# USR_IO_IPMI.net
KiCad netlist of a schematic drawn in Altium Designer
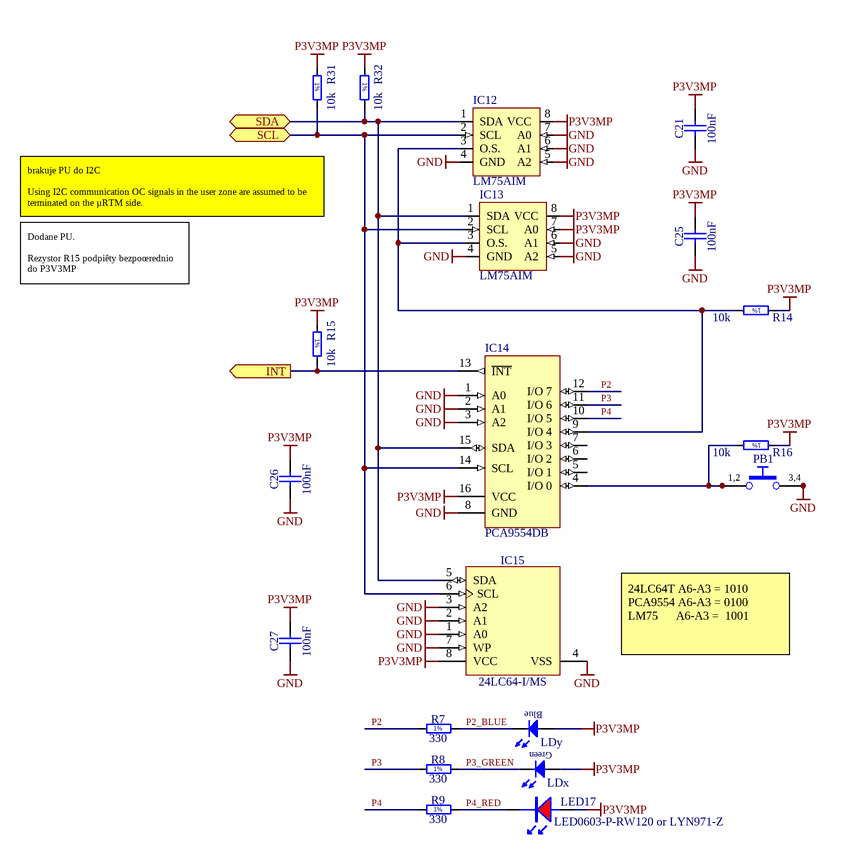
[diagram p0: USR_IO_IPMI.SchDoc]

(export (version "E")
  (design (tool "Eeschema 10.0.6"))
  (components
    (comp (ref "C21")
      (value "100nF")
      (footprint "CAPC1005X55N")
      (description "Non-polarised capacitor")
      (fields
        (field (name "PART NUMBER") "CC0402_100NF_16V_10%_X7R")
        (field (name "VOLTAGE") "16V")
        (field (name "AUTHOR") "CERN DEM JLC")
      )
      (libsource (lib "Capacitors") (part "Capacitor - non polarized"))
    )
    (comp (ref "C25")
      (value "100nF")
      (footprint "CAPC1005X55N")
      (description "Non-polarised capacitor")
      (fields
        (field (name "PART NUMBER") "CC0402_100NF_16V_10%_X7R")
        (field (name "VOLTAGE") "16V")
        (field (name "AUTHOR") "CERN DEM JLC")
      )
      (libsource (lib "Capacitors") (part "Capacitor - non polarized"))
    )
    (comp (ref "C26")
      (value "100nF")
      (footprint "CAPC1005X55N")
      (description "Non-polarised capacitor")
      (fields
        (field (name "PART NUMBER") "CC0402_100NF_16V_10%_X7R")
        (field (name "VOLTAGE") "16V")
        (field (name "AUTHOR") "CERN DEM JLC")
      )
      (libsource (lib "Capacitors") (part "Capacitor - non polarized"))
    )
    (comp (ref "C27")
      (value "100nF")
      (footprint "CAPC1005X55N")
      (description "Non-polarised capacitor")
      (fields
        (field (name "PART NUMBER") "CC0402_100NF_16V_10%_X7R")
        (field (name "VOLTAGE") "16V")
        (field (name "AUTHOR") "CERN DEM JLC")
      )
      (libsource (lib "Capacitors") (part "Capacitor - non polarized"))
    )
    (comp (ref "IC12")
      (value "LM75AIM")
      (footprint "SOIC127P600X175-8N")
      (description "I2C temperature sensor")
      (libsource (lib "LIBRARY_SCH") (part "SENS_LM75"))
    )
    (comp (ref "IC13")
      (value "LM75AIM")
      (footprint "SOIC127P600X175-8N")
      (description "I2C temperature sensor")
      (libsource (lib "LIBRARY_SCH") (part "SENS_LM75"))
    )
    (comp (ref "IC14")
      (value "PCA9554DB")
      (footprint "SOP65P640X120-16N")
      (description "8-bit I2C-bus SMBus I/O port with interrupt")
      (libsource (lib "wr_switch") (part "PCA9554D"))
    )
    (comp (ref "IC15")
      (value "24LC64-I/MS")
      (footprint "SOP65P490X110-8N")
      (description "64K I2C Serial EEPROM")
      (fields (field (name "MANUFACTURER") "MICROCHIP TECHNOLOGY") (field (name "AUTHOR") "CERN DEM JLC"))
      (libsource (lib "ICs And Semiconductors") (part "24LC64-I/MS"))
    )
    (comp (ref "LDx")
      (value "Green")
      (footprint "LED_AVAGO_HSME-C120")
      (description "LED Green Avago C120")
      (fields
        (field (name "PART NUMBER") "LED_AVAGO_HSME-C120")
        (field (name "MANUFACTURER") "AVAGO TECHNOLOGIES")
        (field (name "AUTHOR") "CERN DEM JMW")
      )
      (libsource (lib "LIBRARY_SCH") (part "LED_SMD_90deg_mini_G"))
    )
    (comp (ref "LDy")
      (value "Blue")
      (footprint "LED_AVAGO_HSME-C120")
      (description "LED Blue Avago C120")
      (fields
        (field (name "PART NUMBER") "LED_AVAGO_HSMR-C120")
        (field (name "MANUFACTURER") "AVAGO TECHNOLOGIES")
        (field (name "AUTHOR") "CERN DEM JMW")
      )
      (libsource (lib "LIBRARY_SCH") (part "LED_SMD_90deg_mini_B"))
    )
    (comp (ref "LED17")
      (value "LED0603-P-RW120 or LYN971-Z")
      (footprint "led_0603R")
      (description "LED 0603 red")
      (libsource (lib "LIBRARY_SCH") (part "LED_0603R"))
    )
    (comp (ref "PB1")
      (value "Push Button")
      (footprint "SW_C&K_HDT0001")
      (description "Push-Button Switch SPDT")
      (fields
        (field (name "PART NUMBER") "SW_C&K_HDT0001")
        (field (name "MANUFACTURER") "C&K")
        (field (name "AUTHOR") "CERN DEM JLC")
      )
      (libsource (lib "Eletro-mechanical") (part "PB SPST 12NO-34NO"))
    )
    (comp (ref "R7")
      (value "330")
      (footprint "RESC1608X55N")
      (description "Resistor - 1%")
      (fields
        (field (name "PART NUMBER") "R0603_330R_1%_0.1W_100PPM")
        (field (name "POWER") "0.1W")
        (field (name "AUTHOR") "CERN DEM JLC")
      )
      (libsource (lib "Resistors") (part "Resistor - 1%"))
    )
    (comp (ref "R8")
      (value "330")
      (footprint "RESC1608X55N")
      (description "Resistor - 1%")
      (fields
        (field (name "PART NUMBER") "R0603_330R_1%_0.1W_100PPM")
        (field (name "POWER") "0.1W")
        (field (name "AUTHOR") "CERN DEM JLC")
      )
      (libsource (lib "Resistors") (part "Resistor - 1%"))
    )
    (comp (ref "R9")
      (value "330")
      (footprint "RESC1608X55N")
      (description "Resistor - 1%")
      (fields
        (field (name "PART NUMBER") "R0603_330R_1%_0.1W_100PPM")
        (field (name "POWER") "0.1W")
        (field (name "AUTHOR") "CERN DEM JLC")
      )
      (libsource (lib "Resistors") (part "Resistor - 1%"))
    )
    (comp (ref "R14")
      (value "10k")
      (footprint "RESC1005X40N")
      (description "Resistor - 1%")
      (fields
        (field (name "PART NUMBER") "R0402_10K_1%_0.0625W_100PPM")
        (field (name "POWER") "0.0625W")
        (field (name "AUTHOR") "CERN DEM JLC")
      )
      (libsource (lib "Resistors") (part "Resistor - 1%"))
    )
    (comp (ref "R15")
      (value "10k")
      (footprint "RESC1005X40N")
      (description "Resistor - 1%")
      (fields
        (field (name "PART NUMBER") "R0402_10K_1%_0.0625W_100PPM")
        (field (name "POWER") "0.0625W")
        (field (name "AUTHOR") "CERN DEM JLC")
      )
      (libsource (lib "Resistors") (part "Resistor - 1%"))
    )
    (comp (ref "R16")
      (value "10k")
      (footprint "RESC1005X40N")
      (description "Resistor - 1%")
      (fields
        (field (name "PART NUMBER") "R0402_10K_1%_0.0625W_100PPM")
        (field (name "POWER") "0.0625W")
        (field (name "AUTHOR") "CERN DEM JLC")
      )
      (libsource (lib "Resistors") (part "Resistor - 1%"))
    )
    (comp (ref "R31")
      (value "10k")
      (footprint "RESC1005X40N")
      (description "Resistor - 1%")
      (fields
        (field (name "PART NUMBER") "R0402_10K_1%_0.0625W_100PPM")
        (field (name "POWER") "0.0625W")
        (field (name "AUTHOR") "CERN DEM JLC")
      )
      (libsource (lib "Resistors") (part "Resistor - 1%"))
    )
    (comp (ref "R32")
      (value "10k")
      (footprint "RESC1005X40N")
      (description "Resistor - 1%")
      (fields
        (field (name "PART NUMBER") "R0402_10K_1%_0.0625W_100PPM")
        (field (name "POWER") "0.0625W")
        (field (name "AUTHOR") "CERN DEM JLC")
      )
      (libsource (lib "Resistors") (part "Resistor - 1%"))
    )
  )
  (nets
    (net (code "1") (name "/INT") (class "Default")
      (node (ref "IC14") (pin "13") (pinfunction "~{INT}_13") (pintype "output"))
      (node (ref "R15") (pin "2") (pinfunction "2_2") (pintype "passive"))
    )
    (net (code "2") (name "/P2") (class "Default")
      (node (ref "IC14") (pin "12") (pinfunction "I/O_7_12") (pintype "bidirectional"))
      (node (ref "R7") (pin "1") (pinfunction "1_1") (pintype "passive"))
    )
    (net (code "3") (name "/P2_BLUE") (class "Default")
      (node (ref "LDy") (pin "2") (pinfunction "C_2") (pintype "passive"))
      (node (ref "R7") (pin "2") (pinfunction "2_2") (pintype "passive"))
    )
    (net (code "4") (name "/P3") (class "Default")
      (node (ref "IC14") (pin "11") (pinfunction "I/O_6_11") (pintype "bidirectional"))
      (node (ref "R8") (pin "1") (pinfunction "1_1") (pintype "passive"))
    )
    (net (code "5") (name "/P3_GREEN") (class "Default")
      (node (ref "LDx") (pin "2") (pinfunction "C_2") (pintype "passive"))
      (node (ref "R8") (pin "2") (pinfunction "2_2") (pintype "passive"))
    )
    (net (code "6") (name "/P4") (class "Default")
      (node (ref "IC14") (pin "10") (pinfunction "I/O_5_10") (pintype "bidirectional"))
      (node (ref "R9") (pin "1") (pinfunction "1_1") (pintype "passive"))
    )
    (net (code "7") (name "/P4_RED") (class "Default")
      (node (ref "LED17") (pin "K") (pinfunction "K_K") (pintype "passive"))
      (node (ref "R9") (pin "2") (pinfunction "2_2") (pintype "passive"))
    )
    (net (code "8") (name "/SCL") (class "Default")
      (node (ref "IC12") (pin "2") (pinfunction "SCL_2") (pintype "input"))
      (node (ref "IC13") (pin "2") (pinfunction "SCL_2") (pintype "input"))
      (node (ref "IC14") (pin "14") (pinfunction "SCL_14") (pintype "input"))
      (node (ref "IC15") (pin "6") (pinfunction "SCL_6") (pintype "input"))
      (node (ref "R31") (pin "2") (pinfunction "2_2") (pintype "passive"))
    )
    (net (code "9") (name "/SDA") (class "Default")
      (node (ref "IC12") (pin "1") (pinfunction "SDA_1") (pintype "bidirectional"))
      (node (ref "IC13") (pin "1") (pinfunction "SDA_1") (pintype "bidirectional"))
      (node (ref "IC14") (pin "15") (pinfunction "SDA_15") (pintype "bidirectional"))
      (node (ref "IC15") (pin "5") (pinfunction "SDA_5") (pintype "bidirectional"))
      (node (ref "R32") (pin "2") (pinfunction "2_2") (pintype "passive"))
    )
    (net (code "10") (name "GND") (class "Default")
      (node (ref "C21") (pin "2") (pinfunction "2_2") (pintype "passive"))
      (node (ref "C25") (pin "2") (pinfunction "2_2") (pintype "passive"))
      (node (ref "C26") (pin "2") (pinfunction "2_2") (pintype "passive"))
      (node (ref "C27") (pin "2") (pinfunction "2_2") (pintype "passive"))
      (node (ref "IC12") (pin "4") (pinfunction "GND_4") (pintype "power_in"))
      (node (ref "IC12") (pin "5") (pinfunction "A2_5") (pintype "input"))
      (node (ref "IC12") (pin "6") (pinfunction "A1_6") (pintype "input"))
      (node (ref "IC12") (pin "7") (pinfunction "A0_7") (pintype "input"))
      (node (ref "IC13") (pin "4") (pinfunction "GND_4") (pintype "power_in"))
      (node (ref "IC13") (pin "5") (pinfunction "A2_5") (pintype "input"))
      (node (ref "IC13") (pin "6") (pinfunction "A1_6") (pintype "input"))
      (node (ref "IC14") (pin "1") (pinfunction "A0_1") (pintype "input"))
      (node (ref "IC14") (pin "2") (pinfunction "A1_2") (pintype "input"))
      (node (ref "IC14") (pin "3") (pinfunction "A2_3") (pintype "input"))
      (node (ref "IC14") (pin "8") (pinfunction "GND_8") (pintype "power_in"))
      (node (ref "IC15") (pin "1") (pinfunction "A0_1") (pintype "input"))
      (node (ref "IC15") (pin "2") (pinfunction "A1_2") (pintype "input"))
      (node (ref "IC15") (pin "3") (pinfunction "A2_3") (pintype "input"))
      (node (ref "IC15") (pin "4") (pinfunction "VSS_4") (pintype "power_in"))
      (node (ref "IC15") (pin "7") (pinfunction "WP_7") (pintype "input"))
      (node (ref "PB1") (pin "3") (pinfunction "3_3") (pintype "passive"))
      (node (ref "PB1") (pin "4") (pinfunction "4_4") (pintype "passive"))
    )
    (net (code "11") (name "Net-(IC12-O.S.)") (class "Default")
      (node (ref "IC12") (pin "3") (pinfunction "O.S._3") (pintype "open_collector"))
      (node (ref "IC13") (pin "3") (pinfunction "O.S._3") (pintype "open_collector"))
      (node (ref "IC14") (pin "9") (pinfunction "I/O_4_9") (pintype "bidirectional"))
      (node (ref "R14") (pin "2") (pinfunction "2_2") (pintype "passive"))
    )
    (net (code "12") (name "Net-(IC14-I{slash}O_0)") (class "Default")
      (node (ref "IC14") (pin "4") (pinfunction "I/O_0_4") (pintype "bidirectional"))
      (node (ref "PB1") (pin "1") (pinfunction "1_1") (pintype "passive"))
      (node (ref "PB1") (pin "2") (pinfunction "2_2") (pintype "passive"))
      (node (ref "R16") (pin "2") (pinfunction "2_2") (pintype "passive"))
    )
    (net (code "13") (name "P3V3MP") (class "Default")
      (node (ref "C21") (pin "1") (pinfunction "1_1") (pintype "passive"))
      (node (ref "C25") (pin "1") (pinfunction "1_1") (pintype "passive"))
      (node (ref "C26") (pin "1") (pinfunction "1_1") (pintype "passive"))
      (node (ref "C27") (pin "1") (pinfunction "1_1") (pintype "passive"))
      (node (ref "IC12") (pin "8") (pinfunction "VCC_8") (pintype "power_in"))
      (node (ref "IC13") (pin "7") (pinfunction "A0_7") (pintype "input"))
      (node (ref "IC13") (pin "8") (pinfunction "VCC_8") (pintype "power_in"))
      (node (ref "IC14") (pin "16") (pinfunction "VCC_16") (pintype "power_in"))
      (node (ref "IC15") (pin "8") (pinfunction "VCC_8") (pintype "power_in"))
      (node (ref "LDx") (pin "1") (pinfunction "A_1") (pintype "passive"))
      (node (ref "LDy") (pin "1") (pinfunction "A_1") (pintype "passive"))
      (node (ref "LED17") (pin "A") (pinfunction "A_A") (pintype "passive"))
      (node (ref "R14") (pin "1") (pinfunction "1_1") (pintype "passive"))
      (node (ref "R15") (pin "1") (pinfunction "1_1") (pintype "passive"))
      (node (ref "R16") (pin "1") (pinfunction "1_1") (pintype "passive"))
      (node (ref "R31") (pin "1") (pinfunction "1_1") (pintype "passive"))
      (node (ref "R32") (pin "1") (pinfunction "1_1") (pintype "passive"))
    )
    (net (code "14") (name "unconnected-(IC14-I{slash}O_1-Pad5)") (class "Default")
      (node (ref "IC14") (pin "5") (pinfunction "I/O_1_5") (pintype "bidirectional"))
    )
    (net (code "15") (name "unconnected-(IC14-I{slash}O_2-Pad6)") (class "Default")
      (node (ref "IC14") (pin "6") (pinfunction "I/O_2_6") (pintype "bidirectional"))
    )
    (net (code "16") (name "unconnected-(IC14-I{slash}O_3-Pad7)") (class "Default")
      (node (ref "IC14") (pin "7") (pinfunction "I/O_3_7") (pintype "bidirectional"))
    )
  )
)
